# Half_Bridges.net
KiCad netlist of a schematic drawn in Altium Designer
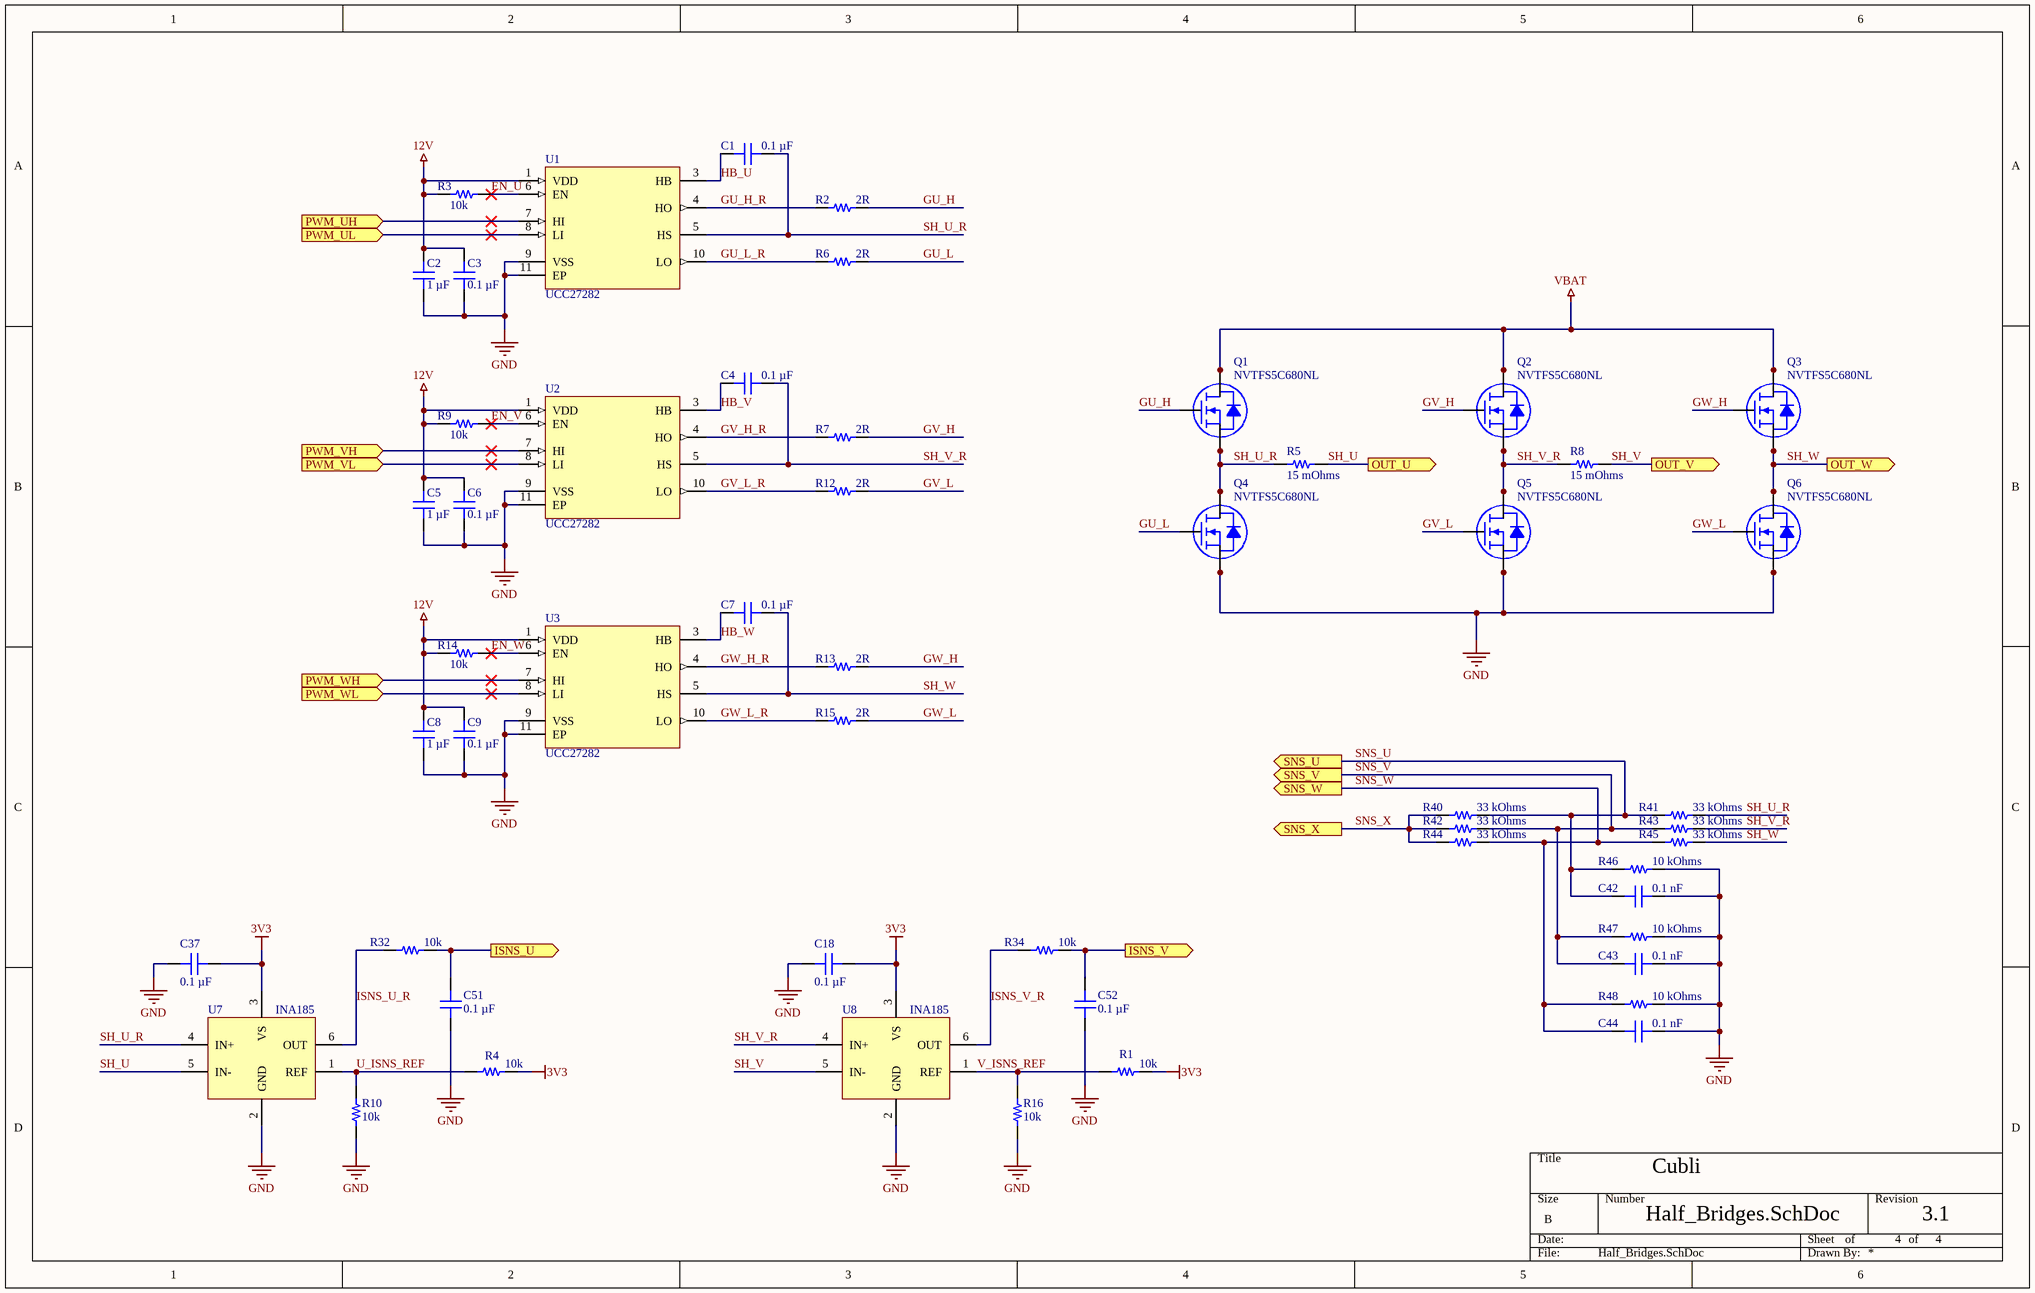
[diagram p0: Half_Bridges.SchDoc]

(export (version "E")
  (design (tool "Eeschema 10.0.6"))
  (components
    (comp (ref "C1")
      (value "0.1 µF")
      (footprint "CAP 0402_1005")
      (description "CAP CER 0.1UF 16V X7R 0402")
      (fields (field (name "PART NUMBER") "C0402C104K4RACAUTO") (field (name "MANUFACTURER") "KEMET"))
      (libsource (lib "Celestial Altium Library - altium_library") (part "Capacitor"))
    )
    (comp (ref "C2")
      (value "1 µF")
      (footprint "CAP 0402_1005")
      (description "CAP CER 0.1UF 16V X7R 0402")
      (fields (field (name "PART NUMBER") "C0402C104K4RACAUTO") (field (name "MANUFACTURER") "KEMET"))
      (libsource (lib "Celestial Altium Library - altium_library") (part "Capacitor"))
    )
    (comp (ref "C3")
      (value "0.1 µF")
      (footprint "CAP 0402_1005")
      (description "CAP CER 0.1UF 16V X7R 0402")
      (fields (field (name "PART NUMBER") "C0402C104K4RACAUTO") (field (name "MANUFACTURER") "KEMET"))
      (libsource (lib "Celestial Altium Library - altium_library") (part "Capacitor"))
    )
    (comp (ref "C4")
      (value "0.1 µF")
      (footprint "CAP 0402_1005")
      (description "CAP CER 0.1UF 16V X7R 0402")
      (fields (field (name "PART NUMBER") "C0402C104K4RACAUTO") (field (name "MANUFACTURER") "KEMET"))
      (libsource (lib "Celestial Altium Library - altium_library") (part "Capacitor"))
    )
    (comp (ref "C5")
      (value "1 µF")
      (footprint "CAP 0402_1005")
      (description "CAP CER 0.1UF 16V X7R 0402")
      (fields (field (name "PART NUMBER") "C0402C104K4RACAUTO") (field (name "MANUFACTURER") "KEMET"))
      (libsource (lib "Celestial Altium Library - altium_library") (part "Capacitor"))
    )
    (comp (ref "C6")
      (value "0.1 µF")
      (footprint "CAP 0402_1005")
      (description "CAP CER 0.1UF 16V X7R 0402")
      (fields (field (name "PART NUMBER") "C0402C104K4RACAUTO") (field (name "MANUFACTURER") "KEMET"))
      (libsource (lib "Celestial Altium Library - altium_library") (part "Capacitor"))
    )
    (comp (ref "C7")
      (value "0.1 µF")
      (footprint "CAP 0402_1005")
      (description "CAP CER 0.1UF 16V X7R 0402")
      (fields (field (name "PART NUMBER") "C0402C104K4RACAUTO") (field (name "MANUFACTURER") "KEMET"))
      (libsource (lib "Celestial Altium Library - altium_library") (part "Capacitor"))
    )
    (comp (ref "C8")
      (value "1 µF")
      (footprint "CAP 0402_1005")
      (description "CAP CER 0.1UF 16V X7R 0402")
      (fields (field (name "PART NUMBER") "C0402C104K4RACAUTO") (field (name "MANUFACTURER") "KEMET"))
      (libsource (lib "Celestial Altium Library - altium_library") (part "Capacitor"))
    )
    (comp (ref "C9")
      (value "0.1 µF")
      (footprint "CAP 0402_1005")
      (description "CAP CER 0.1UF 16V X7R 0402")
      (fields (field (name "PART NUMBER") "C0402C104K4RACAUTO") (field (name "MANUFACTURER") "KEMET"))
      (libsource (lib "Celestial Altium Library - altium_library") (part "Capacitor"))
    )
    (comp (ref "C18")
      (value "0.1 µF")
      (footprint "CAP 0402_1005")
      (description "CAP CER 0.1UF 16V X7R 0402")
      (fields (field (name "PART NUMBER") "C0402C104K4RACAUTO") (field (name "MANUFACTURER") "KEMET"))
      (libsource (lib "Celestial Altium Library - altium_library") (part "Capacitor"))
    )
    (comp (ref "C37")
      (value "0.1 µF")
      (footprint "CAP 0402_1005")
      (description "CAP CER 0.1UF 16V X7R 0402")
      (fields (field (name "PART NUMBER") "C0402C104K4RACAUTO") (field (name "MANUFACTURER") "KEMET"))
      (libsource (lib "Celestial Altium Library - altium_library") (part "Capacitor"))
    )
    (comp (ref "C42")
      (value "0.1 nF")
      (footprint "CAP 0402_1005")
      (description "CAP CER 0.1UF 16V X7R 0402")
      (fields (field (name "PART NUMBER") "C0402C104K4RACAUTO") (field (name "MANUFACTURER") "KEMET"))
      (libsource (lib "Celestial Altium Library - altium_library") (part "Capacitor"))
    )
    (comp (ref "C43")
      (value "0.1 nF")
      (footprint "CAP 0402_1005")
      (description "CAP CER 0.1UF 16V X7R 0402")
      (fields (field (name "PART NUMBER") "C0402C104K4RACAUTO") (field (name "MANUFACTURER") "KEMET"))
      (libsource (lib "Celestial Altium Library - altium_library") (part "Capacitor"))
    )
    (comp (ref "C44")
      (value "0.1 nF")
      (footprint "CAP 0402_1005")
      (description "CAP CER 0.1UF 16V X7R 0402")
      (fields (field (name "PART NUMBER") "C0402C104K4RACAUTO") (field (name "MANUFACTURER") "KEMET"))
      (libsource (lib "Celestial Altium Library - altium_library") (part "Capacitor"))
    )
    (comp (ref "C51")
      (value "0.1 µF")
      (footprint "CAP 0402_1005")
      (description "CAP CER 0.1UF 16V X7R 0402")
      (fields (field (name "PART NUMBER") "C0402C104K4RACAUTO") (field (name "MANUFACTURER") "KEMET"))
      (libsource (lib "Celestial Altium Library - altium_library") (part "Capacitor"))
    )
    (comp (ref "C52")
      (value "0.1 µF")
      (footprint "CAP 0402_1005")
      (description "CAP CER 0.1UF 16V X7R 0402")
      (fields (field (name "PART NUMBER") "C0402C104K4RACAUTO") (field (name "MANUFACTURER") "KEMET"))
      (libsource (lib "Celestial Altium Library - altium_library") (part "Capacitor"))
    )
    (comp (ref "Q1")
      (value "NVTFS5C680NL")
      (footprint "NVTFS015N04CTAG")
      (description "N-FET")
      (libsource (lib "IC") (part "NVTFS5C680NL"))
    )
    (comp (ref "Q2")
      (value "NVTFS5C680NL")
      (footprint "NVTFS015N04CTAG")
      (description "N-FET")
      (libsource (lib "IC") (part "NVTFS5C680NL"))
    )
    (comp (ref "Q3")
      (value "NVTFS5C680NL")
      (footprint "NVTFS015N04CTAG")
      (description "N-FET")
      (libsource (lib "IC") (part "NVTFS5C680NL"))
    )
    (comp (ref "Q4")
      (value "NVTFS5C680NL")
      (footprint "NVTFS015N04CTAG")
      (description "N-FET")
      (libsource (lib "IC") (part "NVTFS5C680NL"))
    )
    (comp (ref "Q5")
      (value "NVTFS5C680NL")
      (footprint "NVTFS015N04CTAG")
      (description "N-FET")
      (libsource (lib "IC") (part "NVTFS5C680NL"))
    )
    (comp (ref "Q6")
      (value "NVTFS5C680NL")
      (footprint "NVTFS015N04CTAG")
      (description "N-FET")
      (libsource (lib "IC") (part "NVTFS5C680NL"))
    )
    (comp (ref "R1")
      (value "10k")
      (footprint "RES 0402_1005")
      (description "RES 14.3K OHM 1% 1/10W 0402")
      (fields
        (field (name "PART NUMBER") "RK73H1ETTP1432F")
        (field (name "MANUFACTURER") "KOA Speer Electronics, Inc.")
      )
      (libsource (lib "Celestial Altium Library - altium_library") (part "Resistor"))
    )
    (comp (ref "R2")
      (value "2R")
      (footprint "RES 0402_1005")
      (description "RES 14.3K OHM 1% 1/10W 0402")
      (fields
        (field (name "PART NUMBER") "RK73H1ETTP1432F")
        (field (name "MANUFACTURER") "KOA Speer Electronics, Inc.")
      )
      (libsource (lib "Celestial Altium Library - altium_library") (part "Resistor"))
    )
    (comp (ref "R3")
      (value "10k")
      (footprint "RES 0402_1005")
      (description "RES 14.3K OHM 1% 1/10W 0402")
      (fields
        (field (name "PART NUMBER") "RK73H1ETTP1432F")
        (field (name "MANUFACTURER") "KOA Speer Electronics, Inc.")
      )
      (libsource (lib "Celestial Altium Library - altium_library") (part "Resistor"))
    )
    (comp (ref "R4")
      (value "10k")
      (footprint "RES 0402_1005")
      (description "RES 14.3K OHM 1% 1/10W 0402")
      (fields
        (field (name "PART NUMBER") "RK73H1ETTP1432F")
        (field (name "MANUFACTURER") "KOA Speer Electronics, Inc.")
      )
      (libsource (lib "Celestial Altium Library - altium_library") (part "Resistor"))
    )
    (comp (ref "R5")
      (value "15 mOhms")
      (footprint "RES 1206_3216")
      (description "RES 0.039 OHM 1% 3/4W 1206")
      (fields (field (name "PART NUMBER") "KRL1632E-M-R039-F-T5") (field (name "MANUFACTURER") "Susumu"))
      (libsource (lib "Celestial Altium Library - altium_library") (part "Resistor"))
    )
    (comp (ref "R6")
      (value "2R")
      (footprint "RES 0402_1005")
      (description "RES 14.3K OHM 1% 1/10W 0402")
      (fields
        (field (name "PART NUMBER") "RK73H1ETTP1432F")
        (field (name "MANUFACTURER") "KOA Speer Electronics, Inc.")
      )
      (libsource (lib "Celestial Altium Library - altium_library") (part "Resistor"))
    )
    (comp (ref "R7")
      (value "2R")
      (footprint "RES 0402_1005")
      (description "RES 14.3K OHM 1% 1/10W 0402")
      (fields
        (field (name "PART NUMBER") "RK73H1ETTP1432F")
        (field (name "MANUFACTURER") "KOA Speer Electronics, Inc.")
      )
      (libsource (lib "Celestial Altium Library - altium_library") (part "Resistor"))
    )
    (comp (ref "R8")
      (value "15 mOhms")
      (footprint "RES 1206_3216")
      (description "RES 0.039 OHM 1% 3/4W 1206")
      (fields (field (name "PART NUMBER") "KRL1632E-M-R039-F-T5") (field (name "MANUFACTURER") "Susumu"))
      (libsource (lib "Celestial Altium Library - altium_library") (part "Resistor"))
    )
    (comp (ref "R9")
      (value "10k")
      (footprint "RES 0402_1005")
      (description "RES 14.3K OHM 1% 1/10W 0402")
      (fields
        (field (name "PART NUMBER") "RK73H1ETTP1432F")
        (field (name "MANUFACTURER") "KOA Speer Electronics, Inc.")
      )
      (libsource (lib "Celestial Altium Library - altium_library") (part "Resistor"))
    )
    (comp (ref "R10")
      (value "10k")
      (footprint "RES 0402_1005")
      (description "RES 14.3K OHM 1% 1/10W 0402")
      (fields
        (field (name "PART NUMBER") "RK73H1ETTP1432F")
        (field (name "MANUFACTURER") "KOA Speer Electronics, Inc.")
      )
      (libsource (lib "Celestial Altium Library - altium_library") (part "Resistor"))
    )
    (comp (ref "R12")
      (value "2R")
      (footprint "RES 0402_1005")
      (description "RES 14.3K OHM 1% 1/10W 0402")
      (fields
        (field (name "PART NUMBER") "RK73H1ETTP1432F")
        (field (name "MANUFACTURER") "KOA Speer Electronics, Inc.")
      )
      (libsource (lib "Celestial Altium Library - altium_library") (part "Resistor"))
    )
    (comp (ref "R13")
      (value "2R")
      (footprint "RES 0402_1005")
      (description "RES 14.3K OHM 1% 1/10W 0402")
      (fields
        (field (name "PART NUMBER") "RK73H1ETTP1432F")
        (field (name "MANUFACTURER") "KOA Speer Electronics, Inc.")
      )
      (libsource (lib "Celestial Altium Library - altium_library") (part "Resistor"))
    )
    (comp (ref "R14")
      (value "10k")
      (footprint "RES 0402_1005")
      (description "RES 14.3K OHM 1% 1/10W 0402")
      (fields
        (field (name "PART NUMBER") "RK73H1ETTP1432F")
        (field (name "MANUFACTURER") "KOA Speer Electronics, Inc.")
      )
      (libsource (lib "Celestial Altium Library - altium_library") (part "Resistor"))
    )
    (comp (ref "R15")
      (value "2R")
      (footprint "RES 0402_1005")
      (description "RES 14.3K OHM 1% 1/10W 0402")
      (fields
        (field (name "PART NUMBER") "RK73H1ETTP1432F")
        (field (name "MANUFACTURER") "KOA Speer Electronics, Inc.")
      )
      (libsource (lib "Celestial Altium Library - altium_library") (part "Resistor"))
    )
    (comp (ref "R16")
      (value "10k")
      (footprint "RES 0402_1005")
      (description "RES 14.3K OHM 1% 1/10W 0402")
      (fields
        (field (name "PART NUMBER") "RK73H1ETTP1432F")
        (field (name "MANUFACTURER") "KOA Speer Electronics, Inc.")
      )
      (libsource (lib "Celestial Altium Library - altium_library") (part "Resistor"))
    )
    (comp (ref "R32")
      (value "10k")
      (footprint "RES 0402_1005")
      (description "RES 14.3K OHM 1% 1/10W 0402")
      (fields
        (field (name "PART NUMBER") "RK73H1ETTP1432F")
        (field (name "MANUFACTURER") "KOA Speer Electronics, Inc.")
      )
      (libsource (lib "Celestial Altium Library - altium_library") (part "Resistor"))
    )
    (comp (ref "R34")
      (value "10k")
      (footprint "RES 0402_1005")
      (description "RES 14.3K OHM 1% 1/10W 0402")
      (fields
        (field (name "PART NUMBER") "RK73H1ETTP1432F")
        (field (name "MANUFACTURER") "KOA Speer Electronics, Inc.")
      )
      (libsource (lib "Celestial Altium Library - altium_library") (part "Resistor"))
    )
    (comp (ref "R40")
      (value "33 kOhms")
      (footprint "RES 0402_1005")
      (description "RES 14.3K OHM 1% 1/10W 0402")
      (fields
        (field (name "PART NUMBER") "RK73H1ETTP1432F")
        (field (name "MANUFACTURER") "KOA Speer Electronics, Inc.")
      )
      (libsource (lib "Celestial Altium Library - altium_library") (part "Resistor"))
    )
    (comp (ref "R41")
      (value "33 kOhms")
      (footprint "RES 0402_1005")
      (description "RES 14.3K OHM 1% 1/10W 0402")
      (fields
        (field (name "PART NUMBER") "RK73H1ETTP1432F")
        (field (name "MANUFACTURER") "KOA Speer Electronics, Inc.")
      )
      (libsource (lib "Celestial Altium Library - altium_library") (part "Resistor"))
    )
    (comp (ref "R42")
      (value "33 kOhms")
      (footprint "RES 0402_1005")
      (description "RES 14.3K OHM 1% 1/10W 0402")
      (fields
        (field (name "PART NUMBER") "RK73H1ETTP1432F")
        (field (name "MANUFACTURER") "KOA Speer Electronics, Inc.")
      )
      (libsource (lib "Celestial Altium Library - altium_library") (part "Resistor"))
    )
    (comp (ref "R43")
      (value "33 kOhms")
      (footprint "RES 0402_1005")
      (description "RES 14.3K OHM 1% 1/10W 0402")
      (fields
        (field (name "PART NUMBER") "RK73H1ETTP1432F")
        (field (name "MANUFACTURER") "KOA Speer Electronics, Inc.")
      )
      (libsource (lib "Celestial Altium Library - altium_library") (part "Resistor"))
    )
    (comp (ref "R44")
      (value "33 kOhms")
      (footprint "RES 0402_1005")
      (description "RES 14.3K OHM 1% 1/10W 0402")
      (fields
        (field (name "PART NUMBER") "RK73H1ETTP1432F")
        (field (name "MANUFACTURER") "KOA Speer Electronics, Inc.")
      )
      (libsource (lib "Celestial Altium Library - altium_library") (part "Resistor"))
    )
    (comp (ref "R45")
      (value "33 kOhms")
      (footprint "RES 0402_1005")
      (description "RES 14.3K OHM 1% 1/10W 0402")
      (fields
        (field (name "PART NUMBER") "RK73H1ETTP1432F")
        (field (name "MANUFACTURER") "KOA Speer Electronics, Inc.")
      )
      (libsource (lib "Celestial Altium Library - altium_library") (part "Resistor"))
    )
    (comp (ref "R46")
      (value "10 kOhms")
      (footprint "RES 0402_1005")
      (description "RES 14.3K OHM 1% 1/10W 0402")
      (fields
        (field (name "PART NUMBER") "RK73H1ETTP1432F")
        (field (name "MANUFACTURER") "KOA Speer Electronics, Inc.")
      )
      (libsource (lib "Celestial Altium Library - altium_library") (part "Resistor"))
    )
    (comp (ref "R47")
      (value "10 kOhms")
      (footprint "RES 0402_1005")
      (description "RES 14.3K OHM 1% 1/10W 0402")
      (fields
        (field (name "PART NUMBER") "RK73H1ETTP1432F")
        (field (name "MANUFACTURER") "KOA Speer Electronics, Inc.")
      )
      (libsource (lib "Celestial Altium Library - altium_library") (part "Resistor"))
    )
    (comp (ref "R48")
      (value "10 kOhms")
      (footprint "RES 0402_1005")
      (description "RES 14.3K OHM 1% 1/10W 0402")
      (fields
        (field (name "PART NUMBER") "RK73H1ETTP1432F")
        (field (name "MANUFACTURER") "KOA Speer Electronics, Inc.")
      )
      (libsource (lib "Celestial Altium Library - altium_library") (part "Resistor"))
    )
    (comp (ref "U1")
      (value "UCC27282")
      (footprint "VSON-10")
      (description "3-A, 120-V half bridge gate driver with 5-V UVLO, interlock and enable 10-VSON -40 to 125")
      (fields (field (name "MF") "Texas Instruments") (field (name "MP") "UCC27282DRCR"))
      (libsource (lib "IC") (part "UCC27282DRCR"))
    )
    (comp (ref "U2")
      (value "UCC27282")
      (footprint "VSON-10")
      (description "3-A, 120-V half bridge gate driver with 5-V UVLO, interlock and enable 10-VSON -40 to 125")
      (fields (field (name "MF") "Texas Instruments") (field (name "MP") "UCC27282DRCR"))
      (libsource (lib "IC") (part "UCC27282DRCR"))
    )
    (comp (ref "U3")
      (value "UCC27282")
      (footprint "VSON-10")
      (description "3-A, 120-V half bridge gate driver with 5-V UVLO, interlock and enable 10-VSON -40 to 125")
      (fields (field (name "MF") "Texas Instruments") (field (name "MP") "UCC27282DRCR"))
      (libsource (lib "IC") (part "UCC27282DRCR"))
    )
    (comp (ref "U7")
      (value "INA185")
      (footprint "TI SC70-6 DCK")
      (description "INA185A2")
      (libsource (lib "IC") (part "INA185"))
    )
    (comp (ref "U8")
      (value "INA185")
      (footprint "TI SC70-6 DCK")
      (description "INA185A2")
      (libsource (lib "IC") (part "INA185"))
    )
  )
  (nets
    (net (code "1") (name "/EN_U") (class "Default")
      (node (ref "R3") (pin "1") (pinfunction "1_1") (pintype "passive"))
      (node (ref "U1") (pin "6") (pinfunction "EN_6") (pintype "input"))
    )
    (net (code "2") (name "/EN_V") (class "Default")
      (node (ref "R9") (pin "1") (pinfunction "1_1") (pintype "passive"))
      (node (ref "U2") (pin "6") (pinfunction "EN_6") (pintype "input"))
    )
    (net (code "3") (name "/EN_W") (class "Default")
      (node (ref "R14") (pin "1") (pinfunction "1_1") (pintype "passive"))
      (node (ref "U3") (pin "6") (pinfunction "EN_6") (pintype "input"))
    )
    (net (code "4") (name "/GU_H") (class "Default")
      (node (ref "Q1") (pin "4") (pinfunction "G_4") (pintype "passive"))
      (node (ref "R2") (pin "1") (pinfunction "1_1") (pintype "passive"))
    )
    (net (code "5") (name "/GU_H_R") (class "Default")
      (node (ref "R2") (pin "2") (pinfunction "2_2") (pintype "passive"))
      (node (ref "U1") (pin "4") (pinfunction "HO_4") (pintype "output"))
    )
    (net (code "6") (name "/GU_L") (class "Default")
      (node (ref "Q4") (pin "4") (pinfunction "G_4") (pintype "passive"))
      (node (ref "R6") (pin "1") (pinfunction "1_1") (pintype "passive"))
    )
    (net (code "7") (name "/GU_L_R") (class "Default")
      (node (ref "R6") (pin "2") (pinfunction "2_2") (pintype "passive"))
      (node (ref "U1") (pin "10") (pinfunction "LO_10") (pintype "output"))
    )
    (net (code "8") (name "/GV_H") (class "Default")
      (node (ref "Q2") (pin "4") (pinfunction "G_4") (pintype "passive"))
      (node (ref "R7") (pin "1") (pinfunction "1_1") (pintype "passive"))
    )
    (net (code "9") (name "/GV_H_R") (class "Default")
      (node (ref "R7") (pin "2") (pinfunction "2_2") (pintype "passive"))
      (node (ref "U2") (pin "4") (pinfunction "HO_4") (pintype "output"))
    )
    (net (code "10") (name "/GV_L") (class "Default")
      (node (ref "Q5") (pin "4") (pinfunction "G_4") (pintype "passive"))
      (node (ref "R12") (pin "1") (pinfunction "1_1") (pintype "passive"))
    )
    (net (code "11") (name "/GV_L_R") (class "Default")
      (node (ref "R12") (pin "2") (pinfunction "2_2") (pintype "passive"))
      (node (ref "U2") (pin "10") (pinfunction "LO_10") (pintype "output"))
    )
    (net (code "12") (name "/GW_H") (class "Default")
      (node (ref "Q3") (pin "4") (pinfunction "G_4") (pintype "passive"))
      (node (ref "R13") (pin "1") (pinfunction "1_1") (pintype "passive"))
    )
    (net (code "13") (name "/GW_H_R") (class "Default")
      (node (ref "R13") (pin "2") (pinfunction "2_2") (pintype "passive"))
      (node (ref "U3") (pin "4") (pinfunction "HO_4") (pintype "output"))
    )
    (net (code "14") (name "/GW_L") (class "Default")
      (node (ref "Q6") (pin "4") (pinfunction "G_4") (pintype "passive"))
      (node (ref "R15") (pin "1") (pinfunction "1_1") (pintype "passive"))
    )
    (net (code "15") (name "/GW_L_R") (class "Default")
      (node (ref "R15") (pin "2") (pinfunction "2_2") (pintype "passive"))
      (node (ref "U3") (pin "10") (pinfunction "LO_10") (pintype "output"))
    )
    (net (code "16") (name "/HB_U") (class "Default")
      (node (ref "C1") (pin "2") (pinfunction "2_2") (pintype "passive"))
      (node (ref "U1") (pin "3") (pinfunction "HB_3") (pintype "power_in"))
    )
    (net (code "17") (name "/HB_V") (class "Default")
      (node (ref "C4") (pin "2") (pinfunction "2_2") (pintype "passive"))
      (node (ref "U2") (pin "3") (pinfunction "HB_3") (pintype "power_in"))
    )
    (net (code "18") (name "/HB_W") (class "Default")
      (node (ref "C7") (pin "2") (pinfunction "2_2") (pintype "passive"))
      (node (ref "U3") (pin "3") (pinfunction "HB_3") (pintype "power_in"))
    )
    (net (code "19") (name "/ISNS_U") (class "Default")
      (node (ref "C51") (pin "1") (pinfunction "1_1") (pintype "passive"))
      (node (ref "R32") (pin "2") (pinfunction "2_2") (pintype "passive"))
    )
    (net (code "20") (name "/ISNS_U_R") (class "Default")
      (node (ref "R32") (pin "1") (pinfunction "1_1") (pintype "passive"))
      (node (ref "U7") (pin "6") (pinfunction "OUT_6") (pintype "passive"))
    )
    (net (code "21") (name "/ISNS_V") (class "Default")
      (node (ref "C52") (pin "1") (pinfunction "1_1") (pintype "passive"))
      (node (ref "R34") (pin "2") (pinfunction "2_2") (pintype "passive"))
    )
    (net (code "22") (name "/ISNS_V_R") (class "Default")
      (node (ref "R34") (pin "1") (pinfunction "1_1") (pintype "passive"))
      (node (ref "U8") (pin "6") (pinfunction "OUT_6") (pintype "passive"))
    )
    (net (code "23") (name "/PWM_UH") (class "Default")
      (node (ref "U1") (pin "7") (pinfunction "HI_7") (pintype "input"))
    )
    (net (code "24") (name "/PWM_UL") (class "Default")
      (node (ref "U1") (pin "8") (pinfunction "LI_8") (pintype "input"))
    )
    (net (code "25") (name "/PWM_VH") (class "Default")
      (node (ref "U2") (pin "7") (pinfunction "HI_7") (pintype "input"))
    )
    (net (code "26") (name "/PWM_VL") (class "Default")
      (node (ref "U2") (pin "8") (pinfunction "LI_8") (pintype "input"))
    )
    (net (code "27") (name "/PWM_WH") (class "Default")
      (node (ref "U3") (pin "7") (pinfunction "HI_7") (pintype "input"))
    )
    (net (code "28") (name "/PWM_WL") (class "Default")
      (node (ref "U3") (pin "8") (pinfunction "LI_8") (pintype "input"))
    )
    (net (code "29") (name "/SH_U") (class "Default")
      (node (ref "R5") (pin "2") (pinfunction "2_2") (pintype "passive"))
      (node (ref "U7") (pin "5") (pinfunction "IN-_5") (pintype "passive"))
    )
    (net (code "30") (name "/SH_U_R") (class "Default")
      (node (ref "C1") (pin "1") (pinfunction "1_1") (pintype "passive"))
      (node (ref "Q1") (pin "1") (pinfunction "S_1") (pintype "passive"))
      (node (ref "Q1") (pin "2") (pinfunction "S_2") (pintype "passive"))
      (node (ref "Q1") (pin "3") (pinfunction "S_3") (pintype "passive"))
      (node (ref "Q4") (pin "5") (pinfunction "D_5") (pintype "passive"))
      (node (ref "Q4") (pin "6") (pinfunction "D_6") (pintype "passive"))
      (node (ref "Q4") (pin "7") (pinfunction "D_7") (pintype "passive"))
      (node (ref "Q4") (pin "8") (pinfunction "D_8") (pintype "passive"))
      (node (ref "R41") (pin "2") (pinfunction "2_2") (pintype "passive"))
      (node (ref "R5") (pin "1") (pinfunction "1_1") (pintype "passive"))
      (node (ref "U1") (pin "5") (pinfunction "HS_5") (pintype "power_in"))
      (node (ref "U7") (pin "4") (pinfunction "IN+_4") (pintype "passive"))
    )
    (net (code "31") (name "/SH_V") (class "Default")
      (node (ref "R8") (pin "2") (pinfunction "2_2") (pintype "passive"))
      (node (ref "U8") (pin "5") (pinfunction "IN-_5") (pintype "passive"))
    )
    (net (code "32") (name "/SH_V_R") (class "Default")
      (node (ref "C4") (pin "1") (pinfunction "1_1") (pintype "passive"))
      (node (ref "Q2") (pin "1") (pinfunction "S_1") (pintype "passive"))
      (node (ref "Q2") (pin "2") (pinfunction "S_2") (pintype "passive"))
      (node (ref "Q2") (pin "3") (pinfunction "S_3") (pintype "passive"))
      (node (ref "Q5") (pin "5") (pinfunction "D_5") (pintype "passive"))
      (node (ref "Q5") (pin "6") (pinfunction "D_6") (pintype "passive"))
      (node (ref "Q5") (pin "7") (pinfunction "D_7") (pintype "passive"))
      (node (ref "Q5") (pin "8") (pinfunction "D_8") (pintype "passive"))
      (node (ref "R43") (pin "2") (pinfunction "2_2") (pintype "passive"))
      (node (ref "R8") (pin "1") (pinfunction "1_1") (pintype "passive"))
      (node (ref "U2") (pin "5") (pinfunction "HS_5") (pintype "power_in"))
      (node (ref "U8") (pin "4") (pinfunction "IN+_4") (pintype "passive"))
    )
    (net (code "33") (name "/SH_W") (class "Default")
      (node (ref "C7") (pin "1") (pinfunction "1_1") (pintype "passive"))
      (node (ref "Q3") (pin "1") (pinfunction "S_1") (pintype "passive"))
      (node (ref "Q3") (pin "2") (pinfunction "S_2") (pintype "passive"))
      (node (ref "Q3") (pin "3") (pinfunction "S_3") (pintype "passive"))
      (node (ref "Q6") (pin "5") (pinfunction "D_5") (pintype "passive"))
      (node (ref "Q6") (pin "6") (pinfunction "D_6") (pintype "passive"))
      (node (ref "Q6") (pin "7") (pinfunction "D_7") (pintype "passive"))
      (node (ref "Q6") (pin "8") (pinfunction "D_8") (pintype "passive"))
      (node (ref "R45") (pin "2") (pinfunction "2_2") (pintype "passive"))
      (node (ref "U3") (pin "5") (pinfunction "HS_5") (pintype "power_in"))
    )
    (net (code "34") (name "/SNS_U") (class "Default")
      (node (ref "C42") (pin "2") (pinfunction "2_2") (pintype "passive"))
      (node (ref "R40") (pin "2") (pinfunction "2_2") (pintype "passive"))
      (node (ref "R41") (pin "1") (pinfunction "1_1") (pintype "passive"))
      (node (ref "R46") (pin "2") (pinfunction "2_2") (pintype "passive"))
    )
    (net (code "35") (name "/SNS_V") (class "Default")
      (node (ref "C43") (pin "2") (pinfunction "2_2") (pintype "passive"))
      (node (ref "R42") (pin "2") (pinfunction "2_2") (pintype "passive"))
      (node (ref "R43") (pin "1") (pinfunction "1_1") (pintype "passive"))
      (node (ref "R47") (pin "2") (pinfunction "2_2") (pintype "passive"))
    )
    (net (code "36") (name "/SNS_W") (class "Default")
      (node (ref "C44") (pin "2") (pinfunction "2_2") (pintype "passive"))
      (node (ref "R44") (pin "2") (pinfunction "2_2") (pintype "passive"))
      (node (ref "R45") (pin "1") (pinfunction "1_1") (pintype "passive"))
      (node (ref "R48") (pin "2") (pinfunction "2_2") (pintype "passive"))
    )
    (net (code "37") (name "/SNS_X") (class "Default")
      (node (ref "R40") (pin "1") (pinfunction "1_1") (pintype "passive"))
      (node (ref "R42") (pin "1") (pinfunction "1_1") (pintype "passive"))
      (node (ref "R44") (pin "1") (pinfunction "1_1") (pintype "passive"))
    )
    (net (code "38") (name "/U_ISNS_REF") (class "Default")
      (node (ref "R10") (pin "2") (pinfunction "2_2") (pintype "passive"))
      (node (ref "R4") (pin "1") (pinfunction "1_1") (pintype "passive"))
      (node (ref "U7") (pin "1") (pinfunction "REF_1") (pintype "passive"))
    )
    (net (code "39") (name "/V_ISNS_REF") (class "Default")
      (node (ref "R1") (pin "1") (pinfunction "1_1") (pintype "passive"))
      (node (ref "R16") (pin "2") (pinfunction "2_2") (pintype "passive"))
      (node (ref "U8") (pin "1") (pinfunction "REF_1") (pintype "passive"))
    )
    (net (code "40") (name "3V3") (class "Default")
      (node (ref "C18") (pin "1") (pinfunction "1_1") (pintype "passive"))
      (node (ref "C37") (pin "1") (pinfunction "1_1") (pintype "passive"))
      (node (ref "R1") (pin "2") (pinfunction "2_2") (pintype "passive"))
      (node (ref "R4") (pin "2") (pinfunction "2_2") (pintype "passive"))
      (node (ref "U7") (pin "3") (pinfunction "VS_3") (pintype "passive"))
      (node (ref "U8") (pin "3") (pinfunction "VS_3") (pintype "passive"))
    )
    (net (code "41") (name "12V") (class "Default")
      (node (ref "C2") (pin "1") (pinfunction "1_1") (pintype "passive"))
      (node (ref "C3") (pin "1") (pinfunction "1_1") (pintype "passive"))
      (node (ref "C5") (pin "1") (pinfunction "1_1") (pintype "passive"))
      (node (ref "C6") (pin "1") (pinfunction "1_1") (pintype "passive"))
      (node (ref "C8") (pin "1") (pinfunction "1_1") (pintype "passive"))
      (node (ref "C9") (pin "1") (pinfunction "1_1") (pintype "passive"))
      (node (ref "R14") (pin "2") (pinfunction "2_2") (pintype "passive"))
      (node (ref "R3") (pin "2") (pinfunction "2_2") (pintype "passive"))
      (node (ref "R9") (pin "2") (pinfunction "2_2") (pintype "passive"))
      (node (ref "U1") (pin "1") (pinfunction "VDD_1") (pintype "input"))
      (node (ref "U2") (pin "1") (pinfunction "VDD_1") (pintype "input"))
      (node (ref "U3") (pin "1") (pinfunction "VDD_1") (pintype "input"))
    )
    (net (code "42") (name "GND") (class "Default")
      (node (ref "C18") (pin "2") (pinfunction "2_2") (pintype "passive"))
      (node (ref "C2") (pin "2") (pinfunction "2_2") (pintype "passive"))
      (node (ref "C3") (pin "2") (pinfunction "2_2") (pintype "passive"))
      (node (ref "C37") (pin "2") (pinfunction "2_2") (pintype "passive"))
      (node (ref "C42") (pin "1") (pinfunction "1_1") (pintype "passive"))
      (node (ref "C43") (pin "1") (pinfunction "1_1") (pintype "passive"))
      (node (ref "C44") (pin "1") (pinfunction "1_1") (pintype "passive"))
      (node (ref "C5") (pin "2") (pinfunction "2_2") (pintype "passive"))
      (node (ref "C51") (pin "2") (pinfunction "2_2") (pintype "passive"))
      (node (ref "C52") (pin "2") (pinfunction "2_2") (pintype "passive"))
      (node (ref "C6") (pin "2") (pinfunction "2_2") (pintype "passive"))
      (node (ref "C8") (pin "2") (pinfunction "2_2") (pintype "passive"))
      (node (ref "C9") (pin "2") (pinfunction "2_2") (pintype "passive"))
      (node (ref "Q4") (pin "1") (pinfunction "S_1") (pintype "passive"))
      (node (ref "Q4") (pin "2") (pinfunction "S_2") (pintype "passive"))
      (node (ref "Q4") (pin "3") (pinfunction "S_3") (pintype "passive"))
      (node (ref "Q5") (pin "1") (pinfunction "S_1") (pintype "passive"))
      (node (ref "Q5") (pin "2") (pinfunction "S_2") (pintype "passive"))
      (node (ref "Q5") (pin "3") (pinfunction "S_3") (pintype "passive"))
      (node (ref "Q6") (pin "1") (pinfunction "S_1") (pintype "passive"))
      (node (ref "Q6") (pin "2") (pinfunction "S_2") (pintype "passive"))
      (node (ref "Q6") (pin "3") (pinfunction "S_3") (pintype "passive"))
      (node (ref "R10") (pin "1") (pinfunction "1_1") (pintype "passive"))
      (node (ref "R16") (pin "1") (pinfunction "1_1") (pintype "passive"))
      (node (ref "R46") (pin "1") (pinfunction "1_1") (pintype "passive"))
      (node (ref "R47") (pin "1") (pinfunction "1_1") (pintype "passive"))
      (node (ref "R48") (pin "1") (pinfunction "1_1") (pintype "passive"))
      (node (ref "U1") (pin "11") (pinfunction "EP_11") (pintype "passive"))
      (node (ref "U1") (pin "9") (pinfunction "VSS_9") (pintype "power_in"))
      (node (ref "U2") (pin "11") (pinfunction "EP_11") (pintype "passive"))
      (node (ref "U2") (pin "9") (pinfunction "VSS_9") (pintype "power_in"))
      (node (ref "U3") (pin "11") (pinfunction "EP_11") (pintype "passive"))
      (node (ref "U3") (pin "9") (pinfunction "VSS_9") (pintype "power_in"))
      (node (ref "U7") (pin "2") (pinfunction "GND_2") (pintype "passive"))
      (node (ref "U8") (pin "2") (pinfunction "GND_2") (pintype "passive"))
    )
    (net (code "43") (name "VBAT") (class "Default")
      (node (ref "Q1") (pin "5") (pinfunction "D_5") (pintype "passive"))
      (node (ref "Q1") (pin "6") (pinfunction "D_6") (pintype "passive"))
      (node (ref "Q1") (pin "7") (pinfunction "D_7") (pintype "passive"))
      (node (ref "Q1") (pin "8") (pinfunction "D_8") (pintype "passive"))
      (node (ref "Q2") (pin "5") (pinfunction "D_5") (pintype "passive"))
      (node (ref "Q2") (pin "6") (pinfunction "D_6") (pintype "passive"))
      (node (ref "Q2") (pin "7") (pinfunction "D_7") (pintype "passive"))
      (node (ref "Q2") (pin "8") (pinfunction "D_8") (pintype "passive"))
      (node (ref "Q3") (pin "5") (pinfunction "D_5") (pintype "passive"))
      (node (ref "Q3") (pin "6") (pinfunction "D_6") (pintype "passive"))
      (node (ref "Q3") (pin "7") (pinfunction "D_7") (pintype "passive"))
      (node (ref "Q3") (pin "8") (pinfunction "D_8") (pintype "passive"))
    )
  )
)
